# ESP32.net
KiCad netlist of a schematic drawn in Altium Designer
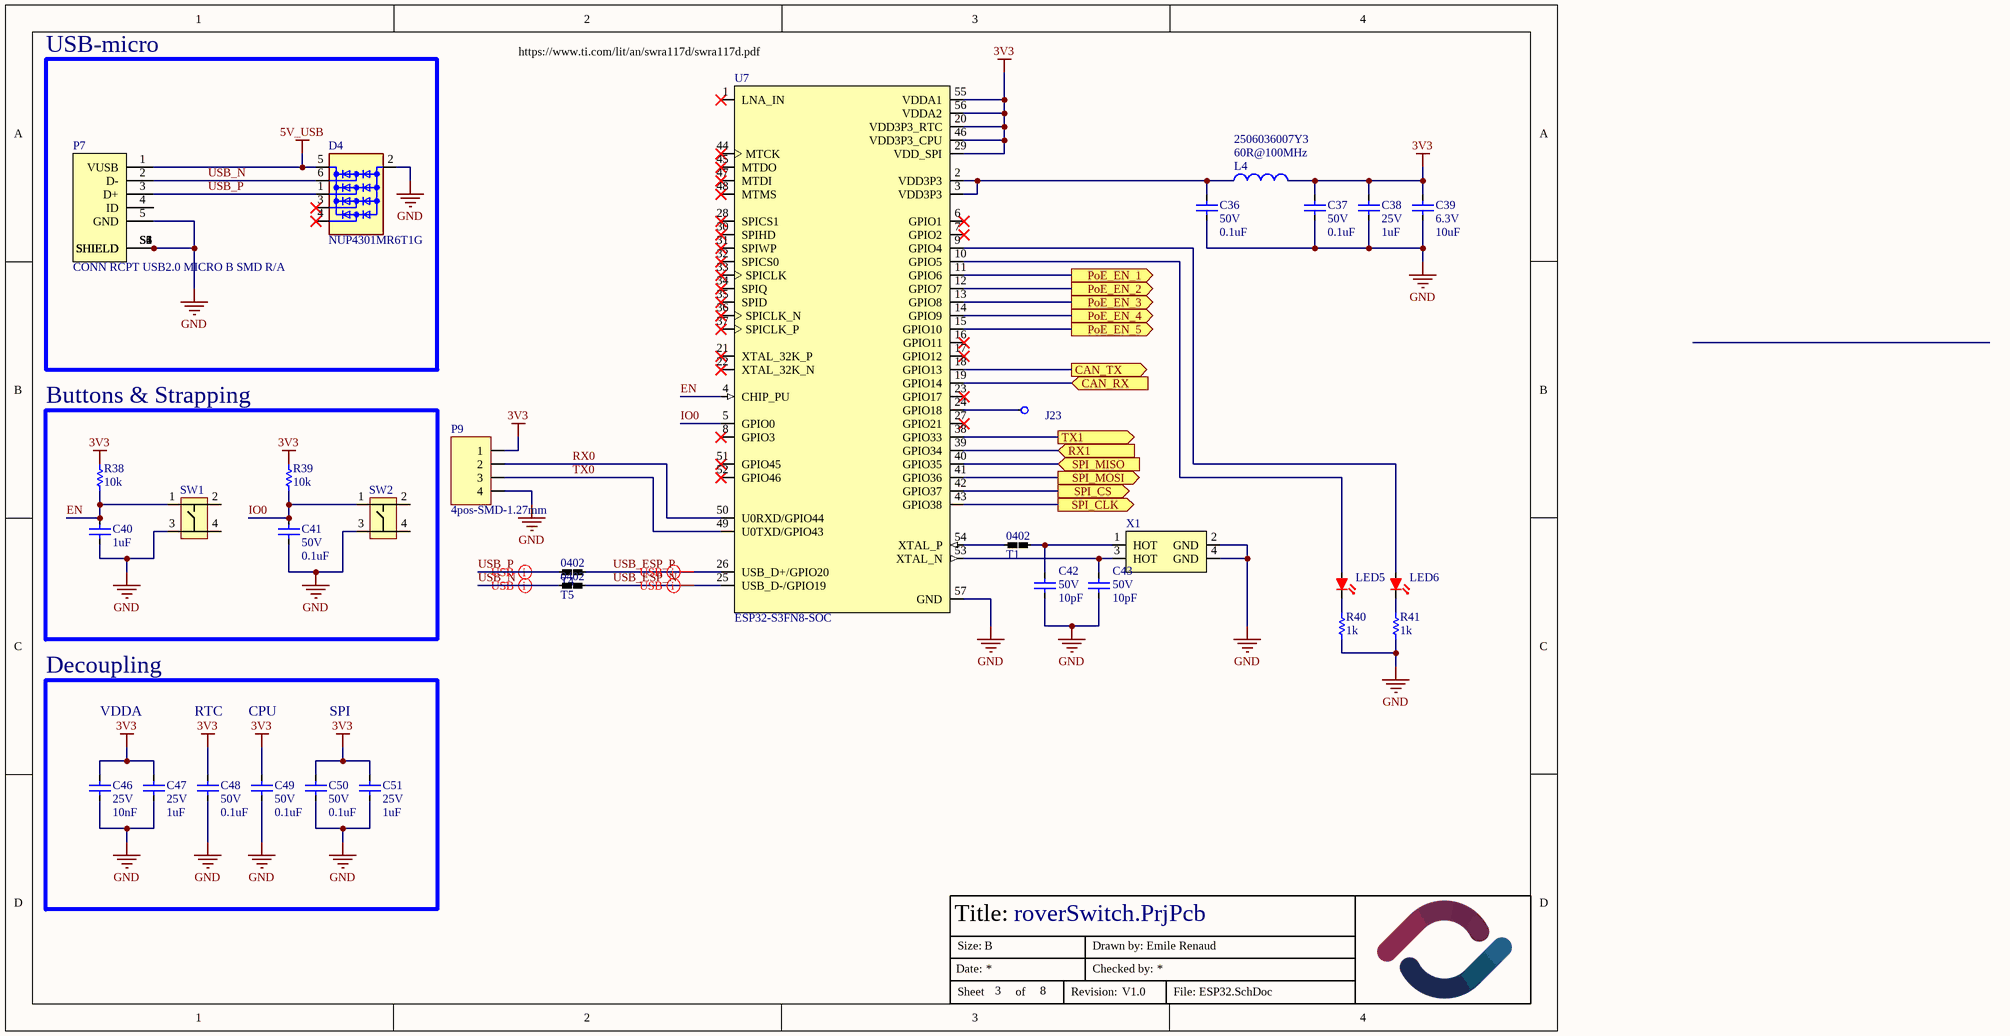
[diagram p0: ESP32.SchDoc]

(export (version "E")
  (design (tool "Eeschema 10.0.6"))
  (components
    (comp (ref "C36")
      (value "0.1uF")
      (footprint "CAPACITOR-0603")
      (description "Capacitor-0603-0.1uF-50V-X7R")
      (fields (field (name "VOLT") "50V"))
      (libsource (lib "Capacitors") (part "Capacitor-0603-0.1uF-50V-X7R"))
    )
    (comp (ref "C37")
      (value "0.1uF")
      (footprint "CAPACITOR-0603")
      (description "Capacitor-0603-0.1uF-50V-X7R")
      (fields (field (name "VOLT") "50V"))
      (libsource (lib "Capacitors") (part "Capacitor-0603-0.1uF-50V-X7R"))
    )
    (comp (ref "C38")
      (value "1uF")
      (footprint "CAPACITOR-0603")
      (description "Capacitor-0603-1uF-25V-X5R")
      (fields (field (name "VOLT") "25V"))
      (libsource (lib "Capacitors") (part "Capacitor-0603-1uF-25V-X5R"))
    )
    (comp (ref "C39")
      (value "10uF")
      (footprint "CAPACITOR-0603")
      (description "Capacitor-0603-10uF-6.3V-X5R, Low ESR, Low ESL")
      (fields (field (name "VOLT") "6.3V") (field (name "Comment") "Capacitor-0603-10uF-6.3V-X5R"))
      (libsource (lib "Capacitors") (part "Capacitor-0603-10uF-6.3V-X5R"))
    )
    (comp (ref "C40")
      (value "1uF")
      (footprint "CAPACITOR-0603")
      (description "Capacitor-0603-1uF-25V-X5R")
      (libsource (lib "Capacitors") (part "Capacitor-0603-1uF-25V-X5R"))
    )
    (comp (ref "C41")
      (value "0.1uF")
      (footprint "CAPACITOR-0603")
      (description "Capacitor-0603-0.1uF-50V-X7R")
      (fields (field (name "VOLT") "50V"))
      (libsource (lib "Capacitors") (part "Capacitor-0603-0.1uF-50V-X7R"))
    )
    (comp (ref "C42")
      (value "10pF")
      (footprint "CAPACITOR-0402")
      (description "Capacitor-0402-10pF-50V-C0G")
      (fields (field (name "VOLT") "50V"))
      (libsource (lib "Capacitors") (part "Capacitor-0402-10pF-50V-C0G"))
    )
    (comp (ref "C43")
      (value "10pF")
      (footprint "CAPACITOR-0402")
      (description "Capacitor-0402-10pF-50V-C0G")
      (fields (field (name "VOLT") "50V"))
      (libsource (lib "Capacitors") (part "Capacitor-0402-10pF-50V-C0G"))
    )
    (comp (ref "C46")
      (value "10nF")
      (footprint "CAPACITOR-0603")
      (description "10000 pF ±10% 25V Ceramic Capacitor X5R 0603 (1608 Metric)")
      (fields (field (name "VOLT") "25V") (field (name "Comment") "Capacitor-0603-10nF-25V-X5R"))
      (libsource (lib "Capacitors") (part "Capacitor-0603-10nF-25V-X5R"))
    )
    (comp (ref "C47")
      (value "1uF")
      (footprint "CAPACITOR-0603")
      (description "Capacitor-0603-1uF-25V-X5R")
      (fields (field (name "VOLT") "25V"))
      (libsource (lib "Capacitors") (part "Capacitor-0603-1uF-25V-X5R"))
    )
    (comp (ref "C48")
      (value "0.1uF")
      (footprint "CAPACITOR-0603")
      (description "Capacitor-0603-0.1uF-50V-X7R")
      (fields (field (name "VOLT") "50V"))
      (libsource (lib "Capacitors") (part "Capacitor-0603-0.1uF-50V-X7R"))
    )
    (comp (ref "C49")
      (value "0.1uF")
      (footprint "CAPACITOR-0603")
      (description "Capacitor-0603-0.1uF-50V-X7R")
      (fields (field (name "VOLT") "50V"))
      (libsource (lib "Capacitors") (part "Capacitor-0603-0.1uF-50V-X7R"))
    )
    (comp (ref "C50")
      (value "0.1uF")
      (footprint "CAPACITOR-0603")
      (description "Capacitor-0603-0.1uF-50V-X7R")
      (fields (field (name "VOLT") "50V"))
      (libsource (lib "Capacitors") (part "Capacitor-0603-0.1uF-50V-X7R"))
    )
    (comp (ref "C51")
      (value "1uF")
      (footprint "CAPACITOR-0603")
      (description "Capacitor-0603-1uF-25V-X5R")
      (fields (field (name "VOLT") "25V"))
      (libsource (lib "Capacitors") (part "Capacitor-0603-1uF-25V-X5R"))
    )
    (comp (ref "D4")
      (value "NUP4301MR6T1G")
      (footprint "SOT-23-6")
      (description "4CH Clamp Ipp Tvs Diode Surface Mount SOT23-6 (SC74)")
      (libsource (lib "diodes") (part "NUP4301MR6T1G"))
    )
    (comp (ref "J23")
      (value "hole")
      (footprint "PCB_Footprints:PAD-0.53MM")
      (description "PAD for 28 AWG Solid Wire")
      (libsource (lib "JumpersAndHoles") (part "PAD 0.53mm AWG28-Solid"))
    )
    (comp (ref "L4")
      (value "2506036007Y3")
      (footprint "CAPACITOR-0603")
      (description "60 Ohms @ 100 MHz 1 Signal Line Ferrite Bead 0603 (1608 Metric) 3A 40mOhm")
      (fields (field (name "ALTIUM_VALUE") "60R@100MHz"))
      (libsource (lib "Inductors") (part "2506036007Y3"))
    )
    (comp (ref "LED5")
      (value "B1911USD-20D000114U1930")
      (footprint "LED-0603-2PIN")
      (description "LED RED CLEAR 1608 SMD")
      (libsource (lib "LEDs") (part "B1911USD-20D000114U1930"))
    )
    (comp (ref "LED6")
      (value "B1911USD-20D000114U1930")
      (footprint "LED-0603-2PIN")
      (description "LED RED CLEAR 1608 SMD")
      (libsource (lib "LEDs") (part "B1911USD-20D000114U1930"))
    )
    (comp (ref "P7")
      (value "CONN RCPT USB2.0 MICRO B SMD R/A")
      (footprint "FCI_10118193-0001LF")
      (description "USB - micro B USB 2.0 Receptacle Connector 5 Position Surface Mount, Right Angle; Through Hole")
      (libsource (lib "PC-connector") (part "USB-Micro"))
    )
    (comp (ref "P9")
      (value "4pos-SMD-1.27mm")
      (footprint "HDR1X4-SMD-50mils")
      (description "4pos SMD 1.27mm")
      (libsource (lib "Header") (part "4pos-SMD-1.27mm"))
    )
    (comp (ref "R38")
      (value "10k")
      (footprint "Resistor-0603")
      (description "Resistor0603-10k")
      (fields (field (name "Comment") "SMT resistor"))
      (libsource (lib "Resistors") (part "Resistor0603-10k"))
    )
    (comp (ref "R39")
      (value "10k")
      (footprint "Resistor-0603")
      (description "Resistor0603-10k")
      (fields (field (name "Comment") "SMT resistor"))
      (libsource (lib "Resistors") (part "Resistor0603-10k"))
    )
    (comp (ref "R40")
      (value "1k")
      (footprint "Resistor-0603")
      (description "Resistor0603-1k")
      (fields (field (name "Comment") "SMT resistor"))
      (libsource (lib "Resistors") (part "Resistor-0603-1k"))
    )
    (comp (ref "R41")
      (value "1k")
      (footprint "Resistor-0603")
      (description "Resistor0603-1k")
      (fields (field (name "Comment") "SMT resistor"))
      (libsource (lib "Resistors") (part "Resistor-0603-1k"))
    )
    (comp (ref "SW1")
      (value "PTS815 SJM 250 SMTR LFS")
      (footprint "SW4_PTS815 SJM 250 SMTR LFS_CNK")
      (description "TACT 4.2 X 3.2, 2.5 MM H, 180GF,")
      (libsource (lib "THTPushButtonSwitches") (part "PTS815 SJM 250 SMTR LFS"))
    )
    (comp (ref "SW2")
      (value "PTS815 SJM 250 SMTR LFS")
      (footprint "SW4_PTS815 SJM 250 SMTR LFS_CNK")
      (description "TACT 4.2 X 3.2, 2.5 MM H, 180GF,")
      (libsource (lib "THTPushButtonSwitches") (part "PTS815 SJM 250 SMTR LFS"))
    )
    (comp (ref "T1")
      (value "NetTie_0402")
      (footprint "NetTie-0402")
      (libsource (lib "JumpersAndHoles") (part "NetTie_0402"))
    )
    (comp (ref "T4")
      (value "NetTie_0402")
      (footprint "NetTie-0402")
      (libsource (lib "JumpersAndHoles") (part "NetTie_0402"))
    )
    (comp (ref "T5")
      (value "NetTie_0402")
      (footprint "NetTie-0402")
      (libsource (lib "JumpersAndHoles") (part "NetTie_0402"))
    )
    (comp (ref "U7")
      (value "ESP32-S3FN8-SOC")
      (footprint "VFQFN-56 Exposed Pad")
      (fields (field (name "MF") "Espressif Systems") (field (name "MP") "ESP32-S3FN8"))
      (libsource (lib "Microcontrollers") (part "ESP32-S3FN8-SOC"))
    )
    (comp (ref "X1")
      (value "CX2016DB40000D0FLJCC")
      (footprint "4-SMD")
      (description "40 MHz ±10ppm Crystal 8pF 50 Ohms 4-SMD, No Lead")
      (libsource (lib "Crystals") (part "CX2016DB40000D0FLJCC"))
    )
  )
  (nets
    (net (code "1") (name "/CAN_RX") (class "Default")
      (node (ref "U7") (pin "19") (pinfunction "GPIO14_19") (pintype "bidirectional"))
    )
    (net (code "2") (name "/CAN_TX") (class "Default")
      (node (ref "U7") (pin "18") (pinfunction "GPIO13_18") (pintype "bidirectional"))
    )
    (net (code "3") (name "/EN") (class "Default")
      (node (ref "C40") (pin "2") (pinfunction "2_2") (pintype "passive"))
      (node (ref "R38") (pin "1") (pinfunction "1_1") (pintype "passive"))
      (node (ref "SW1") (pin "1") (pinfunction "1_1") (pintype "passive"))
      (node (ref "U7") (pin "4") (pinfunction "CHIP_PU_4") (pintype "input"))
    )
    (net (code "4") (name "/IO0") (class "Default")
      (node (ref "C41") (pin "2") (pinfunction "2_2") (pintype "passive"))
      (node (ref "R39") (pin "1") (pinfunction "1_1") (pintype "passive"))
      (node (ref "SW2") (pin "1") (pinfunction "1_1") (pintype "passive"))
      (node (ref "U7") (pin "5") (pinfunction "GPIO0_5") (pintype "bidirectional"))
    )
    (net (code "5") (name "/PoE_EN_1") (class "Default")
      (node (ref "U7") (pin "11") (pinfunction "GPIO6_11") (pintype "bidirectional"))
    )
    (net (code "6") (name "/PoE_EN_2") (class "Default")
      (node (ref "U7") (pin "12") (pinfunction "GPIO7_12") (pintype "bidirectional"))
    )
    (net (code "7") (name "/PoE_EN_3") (class "Default")
      (node (ref "U7") (pin "13") (pinfunction "GPIO8_13") (pintype "bidirectional"))
    )
    (net (code "8") (name "/PoE_EN_4") (class "Default")
      (node (ref "U7") (pin "14") (pinfunction "GPIO9_14") (pintype "bidirectional"))
    )
    (net (code "9") (name "/PoE_EN_5") (class "Default")
      (node (ref "U7") (pin "15") (pinfunction "GPIO10_15") (pintype "bidirectional"))
    )
    (net (code "10") (name "/RX0") (class "Default")
      (node (ref "P9") (pin "2") (pinfunction "2_2") (pintype "passive"))
      (node (ref "U7") (pin "50") (pinfunction "U0RXD/GPIO44_50") (pintype "bidirectional"))
    )
    (net (code "11") (name "/RX1") (class "Default")
      (node (ref "U7") (pin "39") (pinfunction "GPIO34_39") (pintype "bidirectional"))
    )
    (net (code "12") (name "/SPI_CLK") (class "Default")
      (node (ref "U7") (pin "43") (pinfunction "GPIO38_43") (pintype "bidirectional"))
    )
    (net (code "13") (name "/SPI_CS") (class "Default")
      (node (ref "U7") (pin "42") (pinfunction "GPIO37_42") (pintype "bidirectional"))
    )
    (net (code "14") (name "/SPI_MISO") (class "Default")
      (node (ref "U7") (pin "40") (pinfunction "GPIO35_40") (pintype "bidirectional"))
    )
    (net (code "15") (name "/SPI_MOSI") (class "Default")
      (node (ref "U7") (pin "41") (pinfunction "GPIO36_41") (pintype "bidirectional"))
    )
    (net (code "16") (name "/TX0") (class "Default")
      (node (ref "P9") (pin "3") (pinfunction "3_3") (pintype "passive"))
      (node (ref "U7") (pin "49") (pinfunction "U0TXD/GPIO43_49") (pintype "bidirectional"))
    )
    (net (code "17") (name "/TX1") (class "Default")
      (node (ref "U7") (pin "38") (pinfunction "GPIO33_38") (pintype "bidirectional"))
    )
    (net (code "18") (name "/USB_ESP_N") (class "Default")
      (node (ref "T5") (pin "1") (pinfunction "1_1") (pintype "passive"))
      (node (ref "U7") (pin "25") (pinfunction "USB_D-/GPIO19_25") (pintype "bidirectional"))
    )
    (net (code "19") (name "/USB_ESP_P") (class "Default")
      (node (ref "T4") (pin "1") (pinfunction "1_1") (pintype "passive"))
      (node (ref "U7") (pin "26") (pinfunction "USB_D+/GPIO20_26") (pintype "bidirectional"))
    )
    (net (code "20") (name "/USB_N") (class "Default")
      (node (ref "D4") (pin "6") (pinfunction "L1_6") (pintype "passive"))
      (node (ref "P7") (pin "2") (pinfunction "D-_2") (pintype "passive"))
      (node (ref "T5") (pin "2") (pinfunction "2_2") (pintype "passive"))
    )
    (net (code "21") (name "/USB_P") (class "Default")
      (node (ref "D4") (pin "1") (pinfunction "L2_1") (pintype "passive"))
      (node (ref "P7") (pin "3") (pinfunction "D+_3") (pintype "passive"))
      (node (ref "T4") (pin "2") (pinfunction "2_2") (pintype "passive"))
    )
    (net (code "22") (name "3V3") (class "Default")
      (node (ref "C37") (pin "2") (pinfunction "2_2") (pintype "passive"))
      (node (ref "C38") (pin "2") (pinfunction "2_2") (pintype "passive"))
      (node (ref "C39") (pin "2") (pinfunction "2_2") (pintype "passive"))
      (node (ref "C46") (pin "2") (pinfunction "2_2") (pintype "passive"))
      (node (ref "C47") (pin "2") (pinfunction "2_2") (pintype "passive"))
      (node (ref "C48") (pin "2") (pinfunction "2_2") (pintype "passive"))
      (node (ref "C49") (pin "2") (pinfunction "2_2") (pintype "passive"))
      (node (ref "C50") (pin "2") (pinfunction "2_2") (pintype "passive"))
      (node (ref "C51") (pin "2") (pinfunction "2_2") (pintype "passive"))
      (node (ref "L4") (pin "2") (pinfunction "2_2") (pintype "passive"))
      (node (ref "P9") (pin "1") (pinfunction "1_1") (pintype "passive"))
      (node (ref "R38") (pin "2") (pinfunction "2_2") (pintype "passive"))
      (node (ref "R39") (pin "2") (pinfunction "2_2") (pintype "passive"))
      (node (ref "U7") (pin "20") (pinfunction "VDD3P3_RTC_20") (pintype "power_in"))
      (node (ref "U7") (pin "29") (pinfunction "VDD_SPI_29") (pintype "power_in"))
      (node (ref "U7") (pin "46") (pinfunction "VDD3P3_CPU_46") (pintype "power_in"))
      (node (ref "U7") (pin "55") (pinfunction "VDDA1_55") (pintype "power_in"))
      (node (ref "U7") (pin "56") (pinfunction "VDDA2_56") (pintype "power_in"))
    )
    (net (code "23") (name "5V_USB") (class "Default")
      (node (ref "D4") (pin "5") (pinfunction "VDD_5") (pintype "passive"))
      (node (ref "P7") (pin "1") (pinfunction "VUSB_1") (pintype "passive"))
    )
    (net (code "24") (name "GND") (class "Default")
      (node (ref "C36") (pin "1") (pinfunction "1_1") (pintype "passive"))
      (node (ref "C37") (pin "1") (pinfunction "1_1") (pintype "passive"))
      (node (ref "C38") (pin "1") (pinfunction "1_1") (pintype "passive"))
      (node (ref "C39") (pin "1") (pinfunction "1_1") (pintype "passive"))
      (node (ref "C40") (pin "1") (pinfunction "1_1") (pintype "passive"))
      (node (ref "C41") (pin "1") (pinfunction "1_1") (pintype "passive"))
      (node (ref "C42") (pin "1") (pinfunction "1_1") (pintype "passive"))
      (node (ref "C43") (pin "1") (pinfunction "1_1") (pintype "passive"))
      (node (ref "C46") (pin "1") (pinfunction "1_1") (pintype "passive"))
      (node (ref "C47") (pin "1") (pinfunction "1_1") (pintype "passive"))
      (node (ref "C48") (pin "1") (pinfunction "1_1") (pintype "passive"))
      (node (ref "C49") (pin "1") (pinfunction "1_1") (pintype "passive"))
      (node (ref "C50") (pin "1") (pinfunction "1_1") (pintype "passive"))
      (node (ref "C51") (pin "1") (pinfunction "1_1") (pintype "passive"))
      (node (ref "D4") (pin "2") (pinfunction "GND_2") (pintype "passive"))
      (node (ref "P7") (pin "5") (pinfunction "GND_5") (pintype "passive"))
      (node (ref "P7") (pin "S1") (pinfunction "SHIELD_S1") (pintype "passive"))
      (node (ref "P7") (pin "S2") (pinfunction "SHIELD_S2") (pintype "passive"))
      (node (ref "P7") (pin "S3") (pinfunction "SHIELD_S3") (pintype "passive"))
      (node (ref "P7") (pin "S4") (pinfunction "SHIELD_S4") (pintype "passive"))
      (node (ref "P7") (pin "S5") (pinfunction "SHIELD_S5") (pintype "passive"))
      (node (ref "P7") (pin "S6") (pinfunction "SHIELD_S6") (pintype "passive"))
      (node (ref "P9") (pin "4") (pinfunction "4_4") (pintype "passive"))
      (node (ref "R40") (pin "1") (pinfunction "1_1") (pintype "passive"))
      (node (ref "R41") (pin "1") (pinfunction "1_1") (pintype "passive"))
      (node (ref "SW1") (pin "3") (pinfunction "3_3") (pintype "passive"))
      (node (ref "SW2") (pin "3") (pinfunction "3_3") (pintype "passive"))
      (node (ref "U7") (pin "57") (pinfunction "GND_57") (pintype "power_in"))
      (node (ref "X1") (pin "2") (pinfunction "GND_2") (pintype "passive"))
      (node (ref "X1") (pin "4") (pinfunction "GND_4") (pintype "passive"))
    )
    (net (code "25") (name "Net-(C36-Pad2)") (class "Default")
      (node (ref "C36") (pin "2") (pinfunction "2_2") (pintype "passive"))
      (node (ref "L4") (pin "1") (pinfunction "1_1") (pintype "passive"))
      (node (ref "U7") (pin "2") (pinfunction "VDD3P3_2") (pintype "power_in"))
      (node (ref "U7") (pin "3") (pinfunction "VDD3P3_3") (pintype "power_in"))
    )
    (net (code "26") (name "Net-(C42-Pad2)") (class "Default")
      (node (ref "C42") (pin "2") (pinfunction "2_2") (pintype "passive"))
      (node (ref "T1") (pin "1") (pinfunction "1_1") (pintype "passive"))
      (node (ref "X1") (pin "1") (pinfunction "HOT_1") (pintype "passive"))
    )
    (net (code "27") (name "Net-(LED5-K)") (class "Default")
      (node (ref "LED5") (pin "1") (pinfunction "K_1") (pintype "passive"))
      (node (ref "R40") (pin "2") (pinfunction "2_2") (pintype "passive"))
    )
    (net (code "28") (name "Net-(LED5-R)") (class "Default")
      (node (ref "LED5") (pin "2") (pinfunction "R_2") (pintype "passive"))
      (node (ref "U7") (pin "10") (pinfunction "GPIO5_10") (pintype "bidirectional"))
    )
    (net (code "29") (name "Net-(LED6-K)") (class "Default")
      (node (ref "LED6") (pin "1") (pinfunction "K_1") (pintype "passive"))
      (node (ref "R41") (pin "2") (pinfunction "2_2") (pintype "passive"))
    )
    (net (code "30") (name "Net-(LED6-R)") (class "Default")
      (node (ref "LED6") (pin "2") (pinfunction "R_2") (pintype "passive"))
      (node (ref "U7") (pin "9") (pinfunction "GPIO4_9") (pintype "bidirectional"))
    )
    (net (code "31") (name "Net-(U7-GPIO18)") (class "Default")
      (node (ref "J23") (pin "1") (pinfunction "1_1") (pintype "passive"))
      (node (ref "U7") (pin "24") (pinfunction "GPIO18_24") (pintype "bidirectional"))
    )
    (net (code "32") (name "Net-(U7-XTAL_N)") (class "Default")
      (node (ref "C43") (pin "2") (pinfunction "2_2") (pintype "passive"))
      (node (ref "U7") (pin "53") (pinfunction "XTAL_N_53") (pintype "output"))
      (node (ref "X1") (pin "3") (pinfunction "HOT_3") (pintype "passive"))
    )
    (net (code "33") (name "Net-(U7-XTAL_P)") (class "Default")
      (node (ref "T1") (pin "2") (pinfunction "2_2") (pintype "passive"))
      (node (ref "U7") (pin "54") (pinfunction "XTAL_P_54") (pintype "input"))
    )
    (net (code "34") (name "unconnected-(D4-L3-Pad3)") (class "Default")
      (node (ref "D4") (pin "3") (pinfunction "L3_3") (pintype "passive+no_connect"))
    )
    (net (code "35") (name "unconnected-(D4-L4-Pad4)") (class "Default")
      (node (ref "D4") (pin "4") (pinfunction "L4_4") (pintype "passive+no_connect"))
    )
    (net (code "36") (name "unconnected-(P7-ID-Pad4)") (class "Default")
      (node (ref "P7") (pin "4") (pinfunction "ID_4") (pintype "passive"))
    )
    (net (code "37") (name "unconnected-(SW1-Pad2)") (class "Default")
      (node (ref "SW1") (pin "2") (pinfunction "2_2") (pintype "passive"))
    )
    (net (code "38") (name "unconnected-(SW1-Pad4)") (class "Default")
      (node (ref "SW1") (pin "4") (pinfunction "4_4") (pintype "passive"))
    )
    (net (code "39") (name "unconnected-(SW2-Pad2)") (class "Default")
      (node (ref "SW2") (pin "2") (pinfunction "2_2") (pintype "passive"))
    )
    (net (code "40") (name "unconnected-(SW2-Pad4)") (class "Default")
      (node (ref "SW2") (pin "4") (pinfunction "4_4") (pintype "passive"))
    )
    (net (code "41") (name "unconnected-(U7-GPIO1-Pad6)") (class "Default")
      (node (ref "U7") (pin "6") (pinfunction "GPIO1_6") (pintype "bidirectional+no_connect"))
    )
    (net (code "42") (name "unconnected-(U7-GPIO2-Pad7)") (class "Default")
      (node (ref "U7") (pin "7") (pinfunction "GPIO2_7") (pintype "bidirectional+no_connect"))
    )
    (net (code "43") (name "unconnected-(U7-GPIO3-Pad8)") (class "Default")
      (node (ref "U7") (pin "8") (pinfunction "GPIO3_8") (pintype "bidirectional+no_connect"))
    )
    (net (code "44") (name "unconnected-(U7-GPIO11-Pad16)") (class "Default")
      (node (ref "U7") (pin "16") (pinfunction "GPIO11_16") (pintype "bidirectional+no_connect"))
    )
    (net (code "45") (name "unconnected-(U7-GPIO12-Pad17)") (class "Default")
      (node (ref "U7") (pin "17") (pinfunction "GPIO12_17") (pintype "bidirectional+no_connect"))
    )
    (net (code "46") (name "unconnected-(U7-GPIO17-Pad23)") (class "Default")
      (node (ref "U7") (pin "23") (pinfunction "GPIO17_23") (pintype "bidirectional+no_connect"))
    )
    (net (code "47") (name "unconnected-(U7-GPIO21-Pad27)") (class "Default")
      (node (ref "U7") (pin "27") (pinfunction "GPIO21_27") (pintype "bidirectional+no_connect"))
    )
    (net (code "48") (name "unconnected-(U7-GPIO45-Pad51)") (class "Default")
      (node (ref "U7") (pin "51") (pinfunction "GPIO45_51") (pintype "bidirectional+no_connect"))
    )
    (net (code "49") (name "unconnected-(U7-GPIO46-Pad52)") (class "Default")
      (node (ref "U7") (pin "52") (pinfunction "GPIO46_52") (pintype "bidirectional+no_connect"))
    )
    (net (code "50") (name "unconnected-(U7-LNA_IN-Pad1)") (class "Default")
      (node (ref "U7") (pin "1") (pinfunction "LNA_IN_1") (pintype "bidirectional+no_connect"))
    )
    (net (code "51") (name "unconnected-(U7-MTCK-Pad44)") (class "Default")
      (node (ref "U7") (pin "44") (pinfunction "MTCK_44") (pintype "bidirectional+no_connect"))
    )
    (net (code "52") (name "unconnected-(U7-MTDI-Pad47)") (class "Default")
      (node (ref "U7") (pin "47") (pinfunction "MTDI_47") (pintype "bidirectional+no_connect"))
    )
    (net (code "53") (name "unconnected-(U7-MTDO-Pad45)") (class "Default")
      (node (ref "U7") (pin "45") (pinfunction "MTDO_45") (pintype "bidirectional+no_connect"))
    )
    (net (code "54") (name "unconnected-(U7-MTMS-Pad48)") (class "Default")
      (node (ref "U7") (pin "48") (pinfunction "MTMS_48") (pintype "bidirectional+no_connect"))
    )
    (net (code "55") (name "unconnected-(U7-SPICLK-Pad33)") (class "Default")
      (node (ref "U7") (pin "33") (pinfunction "SPICLK_33") (pintype "bidirectional+no_connect"))
    )
    (net (code "56") (name "unconnected-(U7-SPICLK_N-Pad36)") (class "Default")
      (node (ref "U7") (pin "36") (pinfunction "SPICLK_N_36") (pintype "bidirectional+no_connect"))
    )
    (net (code "57") (name "unconnected-(U7-SPICLK_P-Pad37)") (class "Default")
      (node (ref "U7") (pin "37") (pinfunction "SPICLK_P_37") (pintype "bidirectional+no_connect"))
    )
    (net (code "58") (name "unconnected-(U7-SPICS0-Pad32)") (class "Default")
      (node (ref "U7") (pin "32") (pinfunction "SPICS0_32") (pintype "bidirectional+no_connect"))
    )
    (net (code "59") (name "unconnected-(U7-SPICS1-Pad28)") (class "Default")
      (node (ref "U7") (pin "28") (pinfunction "SPICS1_28") (pintype "bidirectional+no_connect"))
    )
    (net (code "60") (name "unconnected-(U7-SPID-Pad35)") (class "Default")
      (node (ref "U7") (pin "35") (pinfunction "SPID_35") (pintype "bidirectional+no_connect"))
    )
    (net (code "61") (name "unconnected-(U7-SPIHD-Pad30)") (class "Default")
      (node (ref "U7") (pin "30") (pinfunction "SPIHD_30") (pintype "bidirectional+no_connect"))
    )
    (net (code "62") (name "unconnected-(U7-SPIQ-Pad34)") (class "Default")
      (node (ref "U7") (pin "34") (pinfunction "SPIQ_34") (pintype "bidirectional+no_connect"))
    )
    (net (code "63") (name "unconnected-(U7-SPIWP-Pad31)") (class "Default")
      (node (ref "U7") (pin "31") (pinfunction "SPIWP_31") (pintype "bidirectional+no_connect"))
    )
    (net (code "64") (name "unconnected-(U7-XTAL_32K_N-Pad22)") (class "Default")
      (node (ref "U7") (pin "22") (pinfunction "XTAL_32K_N_22") (pintype "bidirectional+no_connect"))
    )
    (net (code "65") (name "unconnected-(U7-XTAL_32K_P-Pad21)") (class "Default")
      (node (ref "U7") (pin "21") (pinfunction "XTAL_32K_P_21") (pintype "bidirectional+no_connect"))
    )
  )
)
